# SCH_macro-pad_2024-07-25.net
KiCad netlist of a schematic drawn in EasyEDA
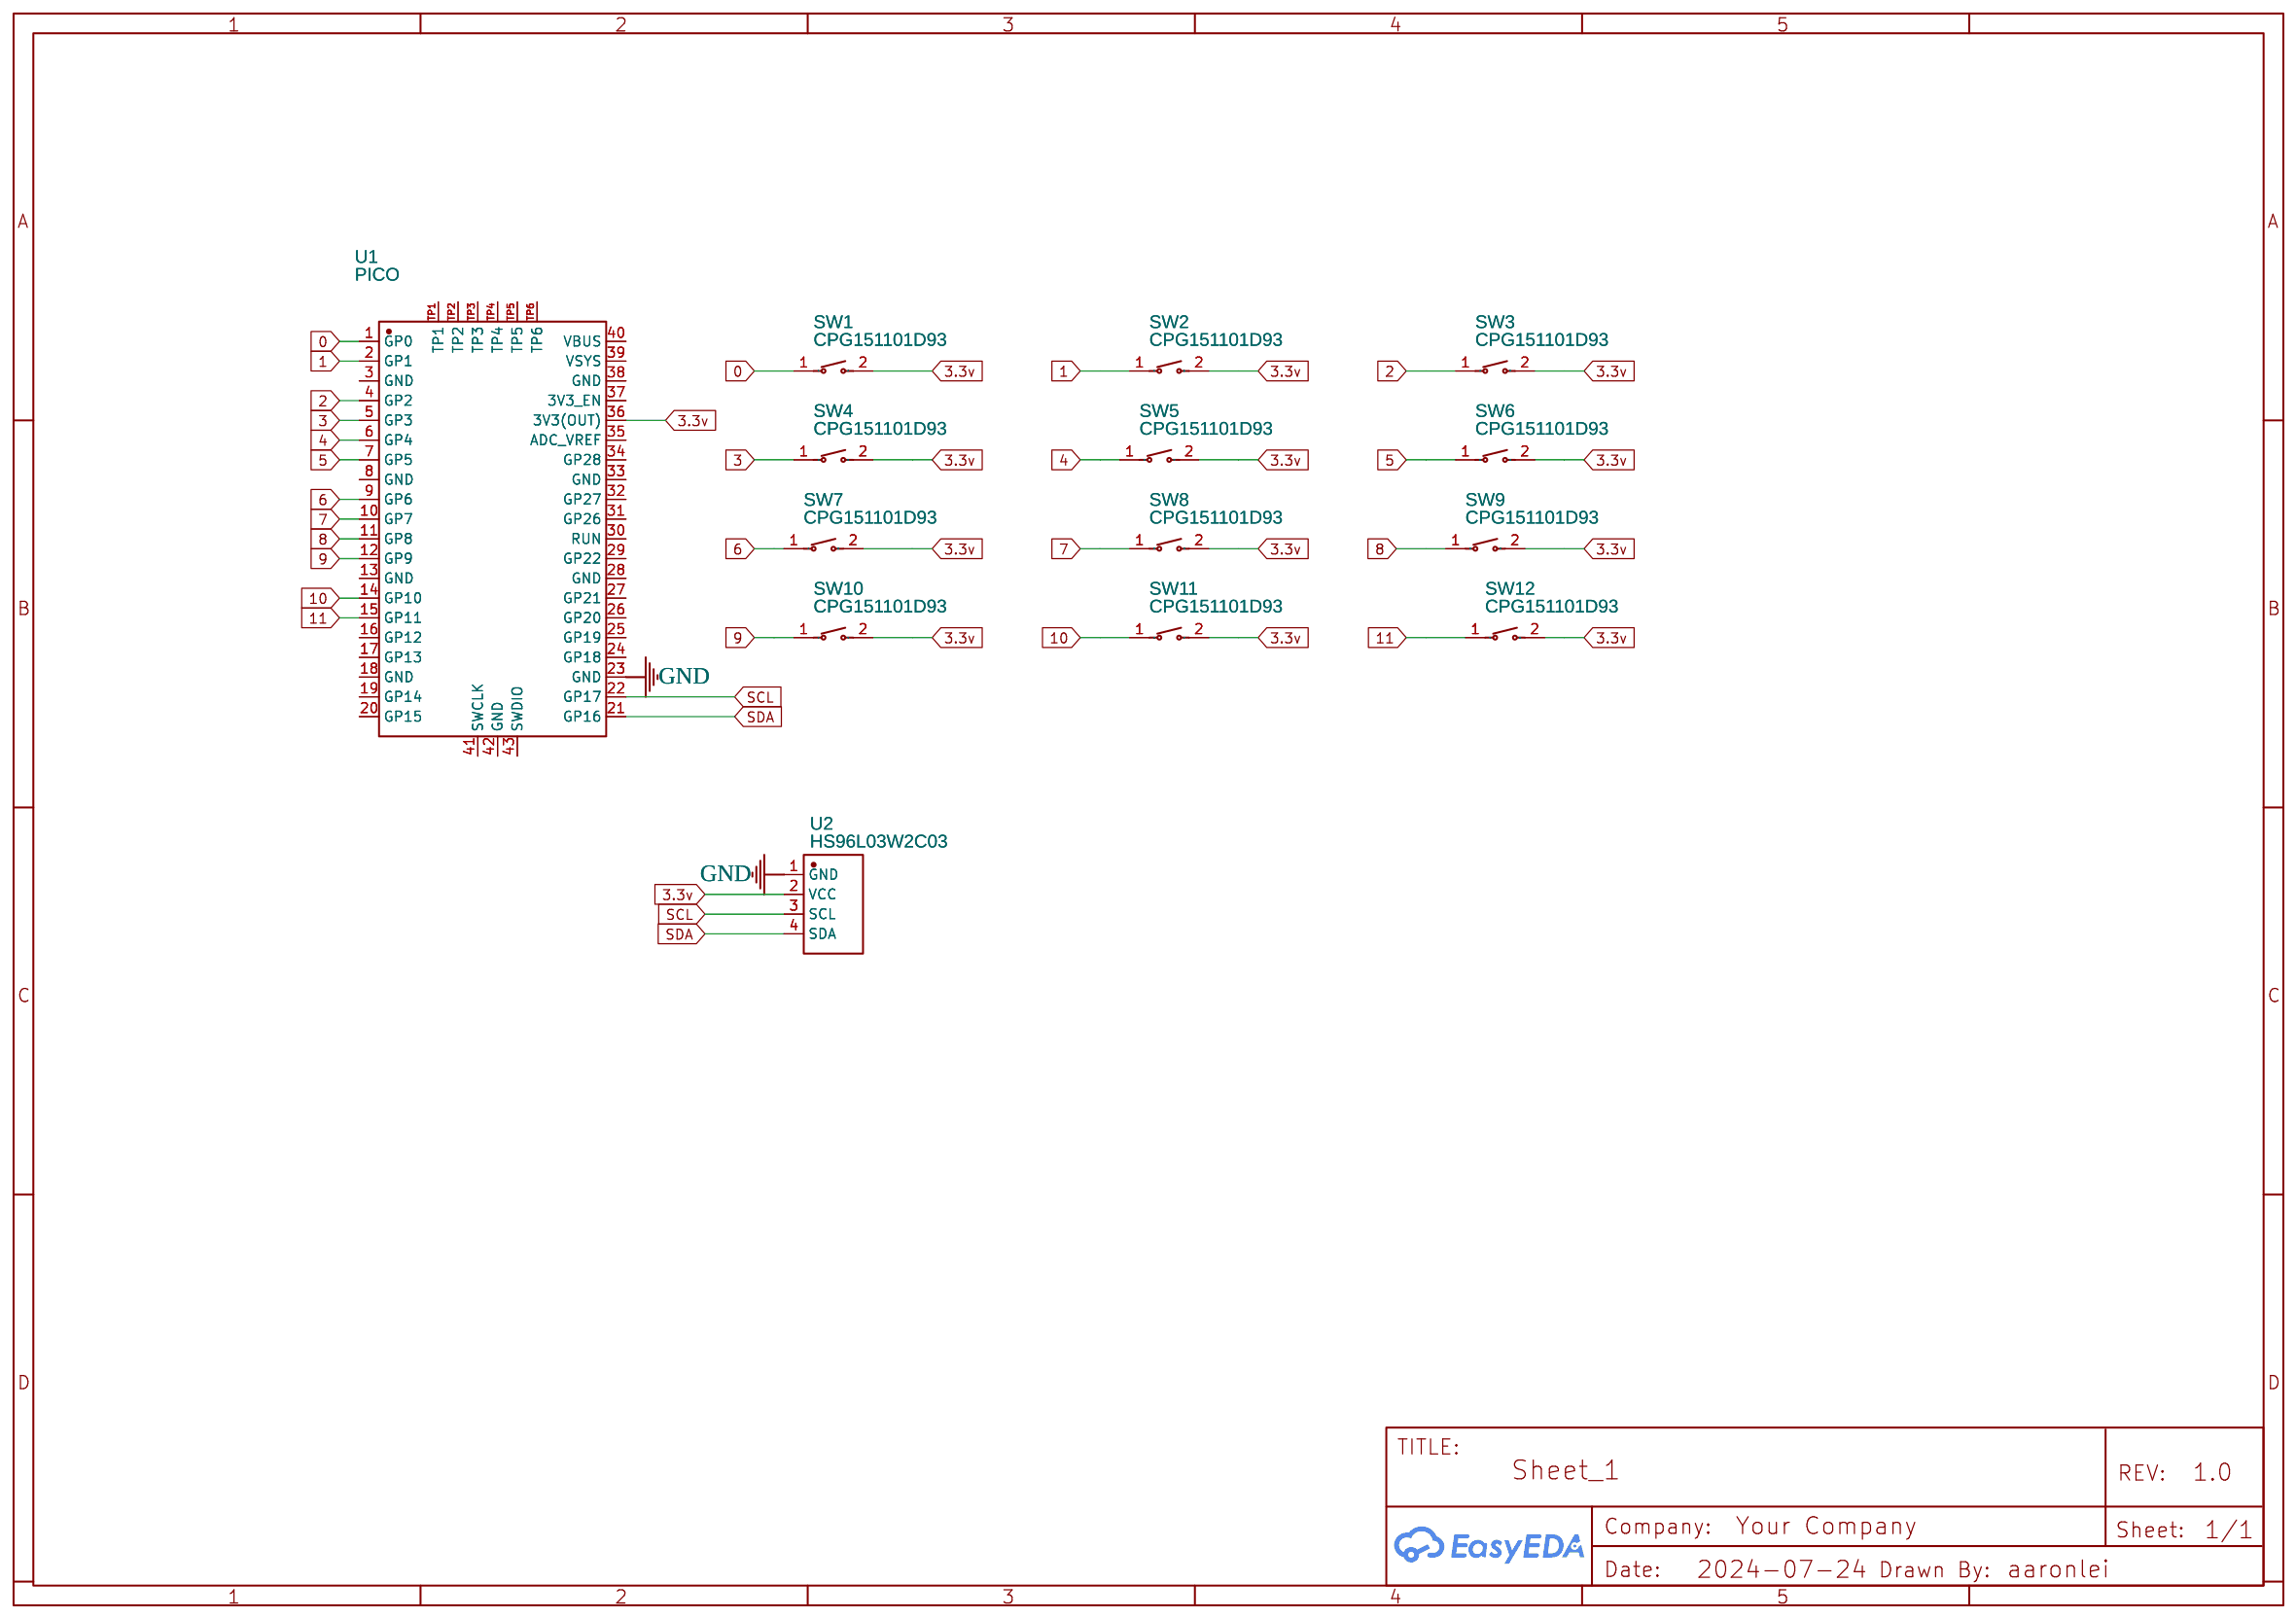
[diagram p0: schematic sheet]

(export (version "E")
  (design (tool "Eeschema 10.0.6"))
  (components
    (comp (ref "SW1")
      (value "CPG151101D93")
      (fields (field (name "Manufacturer") "Kailh(凯华)"))
      (libsource (lib "") (part "CPG151101D93"))
    )
    (comp (ref "SW2")
      (value "CPG151101D93")
      (fields (field (name "Manufacturer") "Kailh(凯华)"))
      (libsource (lib "") (part "CPG151101D93"))
    )
    (comp (ref "SW3")
      (value "CPG151101D93")
      (fields (field (name "Manufacturer") "Kailh(凯华)"))
      (libsource (lib "") (part "CPG151101D93"))
    )
    (comp (ref "SW4")
      (value "CPG151101D93")
      (fields (field (name "Manufacturer") "Kailh(凯华)"))
      (libsource (lib "") (part "CPG151101D93"))
    )
    (comp (ref "SW5")
      (value "CPG151101D93")
      (fields (field (name "Manufacturer") "Kailh(凯华)"))
      (libsource (lib "") (part "CPG151101D93"))
    )
    (comp (ref "SW6")
      (value "CPG151101D93")
      (fields (field (name "Manufacturer") "Kailh(凯华)"))
      (libsource (lib "") (part "CPG151101D93"))
    )
    (comp (ref "SW7")
      (value "CPG151101D93")
      (fields (field (name "Manufacturer") "Kailh(凯华)"))
      (libsource (lib "") (part "CPG151101D93"))
    )
    (comp (ref "SW8")
      (value "CPG151101D93")
      (fields (field (name "Manufacturer") "Kailh(凯华)"))
      (libsource (lib "") (part "CPG151101D93"))
    )
    (comp (ref "SW9")
      (value "CPG151101D93")
      (fields (field (name "Manufacturer") "Kailh(凯华)"))
      (libsource (lib "") (part "CPG151101D93"))
    )
    (comp (ref "SW10")
      (value "CPG151101D93")
      (fields (field (name "Manufacturer") "Kailh(凯华)"))
      (libsource (lib "") (part "CPG151101D93"))
    )
    (comp (ref "SW11")
      (value "CPG151101D93")
      (fields (field (name "Manufacturer") "Kailh(凯华)"))
      (libsource (lib "") (part "CPG151101D93"))
    )
    (comp (ref "SW12")
      (value "CPG151101D93")
      (fields (field (name "Manufacturer") "Kailh(凯华)"))
      (libsource (lib "") (part "CPG151101D93"))
    )
    (comp (ref "U1")
      (value "PICO")
      (fields (field (name "Manufacturer") "Raspberry Pi(树莓派)"))
      (libsource (lib "") (part "PICO"))
    )
    (comp (ref "U2")
      (value "HS96L03W2C03")
      (fields (field (name "Manufacturer") "HS(汉昇)"))
      (libsource (lib "") (part "HS96L03W2C03"))
    )
  )
  (nets
    (net (code "1") (name "0") (class "Default")
      (node (ref "SW1") (pin "1") (pinfunction "1_1") (pintype "unspecified"))
      (node (ref "U1") (pin "1") (pinfunction "GP0_1") (pintype "unspecified"))
    )
    (net (code "2") (name "1") (class "Default")
      (node (ref "SW2") (pin "1") (pinfunction "1_1") (pintype "unspecified"))
      (node (ref "U1") (pin "2") (pinfunction "GP1_2") (pintype "unspecified"))
    )
    (net (code "3") (name "2") (class "Default")
      (node (ref "SW3") (pin "1") (pinfunction "1_1") (pintype "unspecified"))
      (node (ref "U1") (pin "4") (pinfunction "GP2_4") (pintype "unspecified"))
    )
    (net (code "4") (name "3") (class "Default")
      (node (ref "SW4") (pin "1") (pinfunction "1_1") (pintype "unspecified"))
      (node (ref "U1") (pin "5") (pinfunction "GP3_5") (pintype "unspecified"))
    )
    (net (code "5") (name "3.3v") (class "Default")
      (node (ref "SW1") (pin "2") (pinfunction "2_2") (pintype "unspecified"))
      (node (ref "SW10") (pin "2") (pinfunction "2_2") (pintype "unspecified"))
      (node (ref "SW11") (pin "2") (pinfunction "2_2") (pintype "unspecified"))
      (node (ref "SW12") (pin "2") (pinfunction "2_2") (pintype "unspecified"))
      (node (ref "SW2") (pin "2") (pinfunction "2_2") (pintype "unspecified"))
      (node (ref "SW3") (pin "2") (pinfunction "2_2") (pintype "unspecified"))
      (node (ref "SW4") (pin "2") (pinfunction "2_2") (pintype "unspecified"))
      (node (ref "SW5") (pin "2") (pinfunction "2_2") (pintype "unspecified"))
      (node (ref "SW6") (pin "2") (pinfunction "2_2") (pintype "unspecified"))
      (node (ref "SW7") (pin "2") (pinfunction "2_2") (pintype "unspecified"))
      (node (ref "SW8") (pin "2") (pinfunction "2_2") (pintype "unspecified"))
      (node (ref "SW9") (pin "2") (pinfunction "2_2") (pintype "unspecified"))
      (node (ref "U1") (pin "36") (pinfunction "3V3(OUT)_36") (pintype "unspecified"))
      (node (ref "U2") (pin "2") (pinfunction "VCC_2") (pintype "unspecified"))
    )
    (net (code "6") (name "4") (class "Default")
      (node (ref "SW5") (pin "1") (pinfunction "1_1") (pintype "unspecified"))
      (node (ref "U1") (pin "6") (pinfunction "GP4_6") (pintype "unspecified"))
    )
    (net (code "7") (name "5") (class "Default")
      (node (ref "SW6") (pin "1") (pinfunction "1_1") (pintype "unspecified"))
      (node (ref "U1") (pin "7") (pinfunction "GP5_7") (pintype "unspecified"))
    )
    (net (code "8") (name "6") (class "Default")
      (node (ref "SW7") (pin "1") (pinfunction "1_1") (pintype "unspecified"))
      (node (ref "U1") (pin "9") (pinfunction "GP6_9") (pintype "unspecified"))
    )
    (net (code "9") (name "7") (class "Default")
      (node (ref "SW8") (pin "1") (pinfunction "1_1") (pintype "unspecified"))
      (node (ref "U1") (pin "10") (pinfunction "GP7_10") (pintype "unspecified"))
    )
    (net (code "10") (name "8") (class "Default")
      (node (ref "SW9") (pin "1") (pinfunction "1_1") (pintype "unspecified"))
      (node (ref "U1") (pin "11") (pinfunction "GP8_11") (pintype "unspecified"))
    )
    (net (code "11") (name "9") (class "Default")
      (node (ref "SW10") (pin "1") (pinfunction "1_1") (pintype "unspecified"))
      (node (ref "U1") (pin "12") (pinfunction "GP9_12") (pintype "unspecified"))
    )
    (net (code "12") (name "10") (class "Default")
      (node (ref "SW11") (pin "1") (pinfunction "1_1") (pintype "unspecified"))
      (node (ref "U1") (pin "14") (pinfunction "GP10_14") (pintype "unspecified"))
    )
    (net (code "13") (name "11") (class "Default")
      (node (ref "SW12") (pin "1") (pinfunction "1_1") (pintype "unspecified"))
      (node (ref "U1") (pin "15") (pinfunction "GP11_15") (pintype "unspecified"))
    )
    (net (code "14") (name "GND") (class "Default")
      (node (ref "U1") (pin "23") (pinfunction "GND_23") (pintype "unspecified"))
      (node (ref "U2") (pin "1") (pinfunction "GND_1") (pintype "unspecified"))
    )
    (net (code "15") (name "SCL") (class "Default")
      (node (ref "U1") (pin "22") (pinfunction "GP17_22") (pintype "unspecified"))
      (node (ref "U2") (pin "3") (pinfunction "SCL_3") (pintype "unspecified"))
    )
    (net (code "16") (name "SDA") (class "Default")
      (node (ref "U1") (pin "21") (pinfunction "GP16_21") (pintype "unspecified"))
      (node (ref "U2") (pin "4") (pinfunction "SDA_4") (pintype "unspecified"))
    )
    (net (code "17") (name "unconnected-(U1-3V3_EN-Pad37)") (class "Default")
      (node (ref "U1") (pin "37") (pinfunction "3V3_EN_37") (pintype "unspecified"))
    )
    (net (code "18") (name "unconnected-(U1-ADC_VREF-Pad35)") (class "Default")
      (node (ref "U1") (pin "35") (pinfunction "ADC_VREF_35") (pintype "unspecified"))
    )
    (net (code "19") (name "unconnected-(U1-GND-Pad3)") (class "Default")
      (node (ref "U1") (pin "3") (pinfunction "GND_3") (pintype "unspecified"))
    )
    (net (code "20") (name "unconnected-(U1-GND-Pad8)") (class "Default")
      (node (ref "U1") (pin "8") (pinfunction "GND_8") (pintype "unspecified"))
    )
    (net (code "21") (name "unconnected-(U1-GND-Pad13)") (class "Default")
      (node (ref "U1") (pin "13") (pinfunction "GND_13") (pintype "unspecified"))
    )
    (net (code "22") (name "unconnected-(U1-GND-Pad18)") (class "Default")
      (node (ref "U1") (pin "18") (pinfunction "GND_18") (pintype "unspecified"))
    )
    (net (code "23") (name "unconnected-(U1-GND-Pad28)") (class "Default")
      (node (ref "U1") (pin "28") (pinfunction "GND_28") (pintype "unspecified"))
    )
    (net (code "24") (name "unconnected-(U1-GND-Pad33)") (class "Default")
      (node (ref "U1") (pin "33") (pinfunction "GND_33") (pintype "unspecified"))
    )
    (net (code "25") (name "unconnected-(U1-GND-Pad38)") (class "Default")
      (node (ref "U1") (pin "38") (pinfunction "GND_38") (pintype "unspecified"))
    )
    (net (code "26") (name "unconnected-(U1-GND-Pad42)") (class "Default")
      (node (ref "U1") (pin "42") (pinfunction "GND_42") (pintype "unspecified"))
    )
    (net (code "27") (name "unconnected-(U1-GP12-Pad16)") (class "Default")
      (node (ref "U1") (pin "16") (pinfunction "GP12_16") (pintype "unspecified"))
    )
    (net (code "28") (name "unconnected-(U1-GP13-Pad17)") (class "Default")
      (node (ref "U1") (pin "17") (pinfunction "GP13_17") (pintype "unspecified"))
    )
    (net (code "29") (name "unconnected-(U1-GP14-Pad19)") (class "Default")
      (node (ref "U1") (pin "19") (pinfunction "GP14_19") (pintype "unspecified"))
    )
    (net (code "30") (name "unconnected-(U1-GP15-Pad20)") (class "Default")
      (node (ref "U1") (pin "20") (pinfunction "GP15_20") (pintype "unspecified"))
    )
    (net (code "31") (name "unconnected-(U1-GP18-Pad24)") (class "Default")
      (node (ref "U1") (pin "24") (pinfunction "GP18_24") (pintype "unspecified"))
    )
    (net (code "32") (name "unconnected-(U1-GP19-Pad25)") (class "Default")
      (node (ref "U1") (pin "25") (pinfunction "GP19_25") (pintype "unspecified"))
    )
    (net (code "33") (name "unconnected-(U1-GP20-Pad26)") (class "Default")
      (node (ref "U1") (pin "26") (pinfunction "GP20_26") (pintype "unspecified"))
    )
    (net (code "34") (name "unconnected-(U1-GP21-Pad27)") (class "Default")
      (node (ref "U1") (pin "27") (pinfunction "GP21_27") (pintype "unspecified"))
    )
    (net (code "35") (name "unconnected-(U1-GP22-Pad29)") (class "Default")
      (node (ref "U1") (pin "29") (pinfunction "GP22_29") (pintype "unspecified"))
    )
    (net (code "36") (name "unconnected-(U1-GP26-Pad31)") (class "Default")
      (node (ref "U1") (pin "31") (pinfunction "GP26_31") (pintype "unspecified"))
    )
    (net (code "37") (name "unconnected-(U1-GP27-Pad32)") (class "Default")
      (node (ref "U1") (pin "32") (pinfunction "GP27_32") (pintype "unspecified"))
    )
    (net (code "38") (name "unconnected-(U1-GP28-Pad34)") (class "Default")
      (node (ref "U1") (pin "34") (pinfunction "GP28_34") (pintype "unspecified"))
    )
    (net (code "39") (name "unconnected-(U1-PadTP1)") (class "Default")
      (node (ref "U1") (pin "TP1") (pinfunction "TP1_TP1") (pintype "unspecified"))
    )
    (net (code "40") (name "unconnected-(U1-PadTP2)") (class "Default")
      (node (ref "U1") (pin "TP2") (pinfunction "TP2_TP2") (pintype "unspecified"))
    )
    (net (code "41") (name "unconnected-(U1-PadTP3)") (class "Default")
      (node (ref "U1") (pin "TP3") (pinfunction "TP3_TP3") (pintype "unspecified"))
    )
    (net (code "42") (name "unconnected-(U1-PadTP4)") (class "Default")
      (node (ref "U1") (pin "TP4") (pinfunction "TP4_TP4") (pintype "unspecified"))
    )
    (net (code "43") (name "unconnected-(U1-PadTP5)") (class "Default")
      (node (ref "U1") (pin "TP5") (pinfunction "TP5_TP5") (pintype "unspecified"))
    )
    (net (code "44") (name "unconnected-(U1-PadTP6)") (class "Default")
      (node (ref "U1") (pin "TP6") (pinfunction "TP6_TP6") (pintype "unspecified"))
    )
    (net (code "45") (name "unconnected-(U1-RUN-Pad30)") (class "Default")
      (node (ref "U1") (pin "30") (pinfunction "RUN_30") (pintype "unspecified"))
    )
    (net (code "46") (name "unconnected-(U1-SWCLK-Pad41)") (class "Default")
      (node (ref "U1") (pin "41") (pinfunction "SWCLK_41") (pintype "unspecified"))
    )
    (net (code "47") (name "unconnected-(U1-SWDIO-Pad43)") (class "Default")
      (node (ref "U1") (pin "43") (pinfunction "SWDIO_43") (pintype "unspecified"))
    )
    (net (code "48") (name "unconnected-(U1-VBUS-Pad40)") (class "Default")
      (node (ref "U1") (pin "40") (pinfunction "VBUS_40") (pintype "unspecified"))
    )
    (net (code "49") (name "unconnected-(U1-VSYS-Pad39)") (class "Default")
      (node (ref "U1") (pin "39") (pinfunction "VSYS_39") (pintype "unspecified"))
    )
  )
)
